# 04_ethernet.net
KiCad netlist of a schematic drawn in Altium Designer
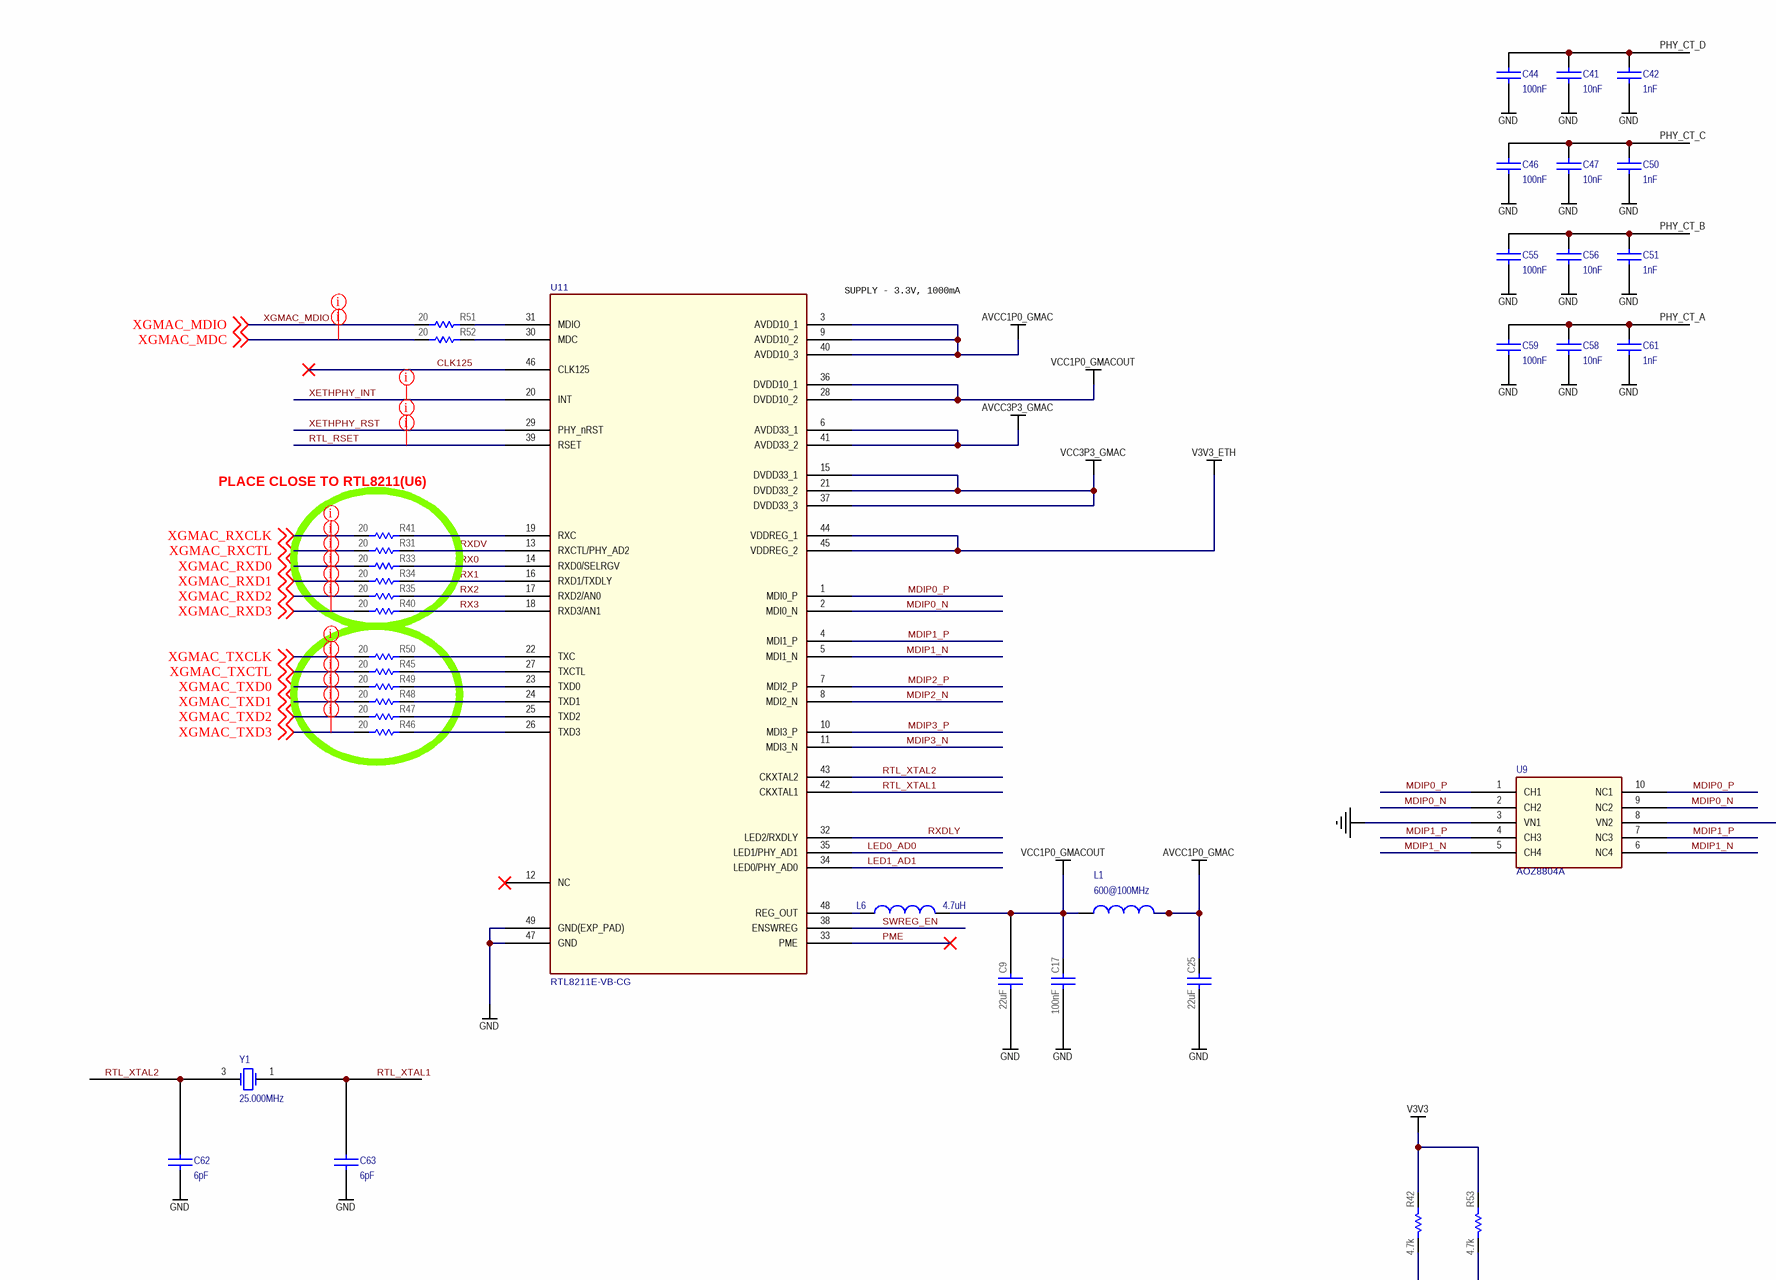
[diagram p0: 04_ethernet.SchDoc, top left]
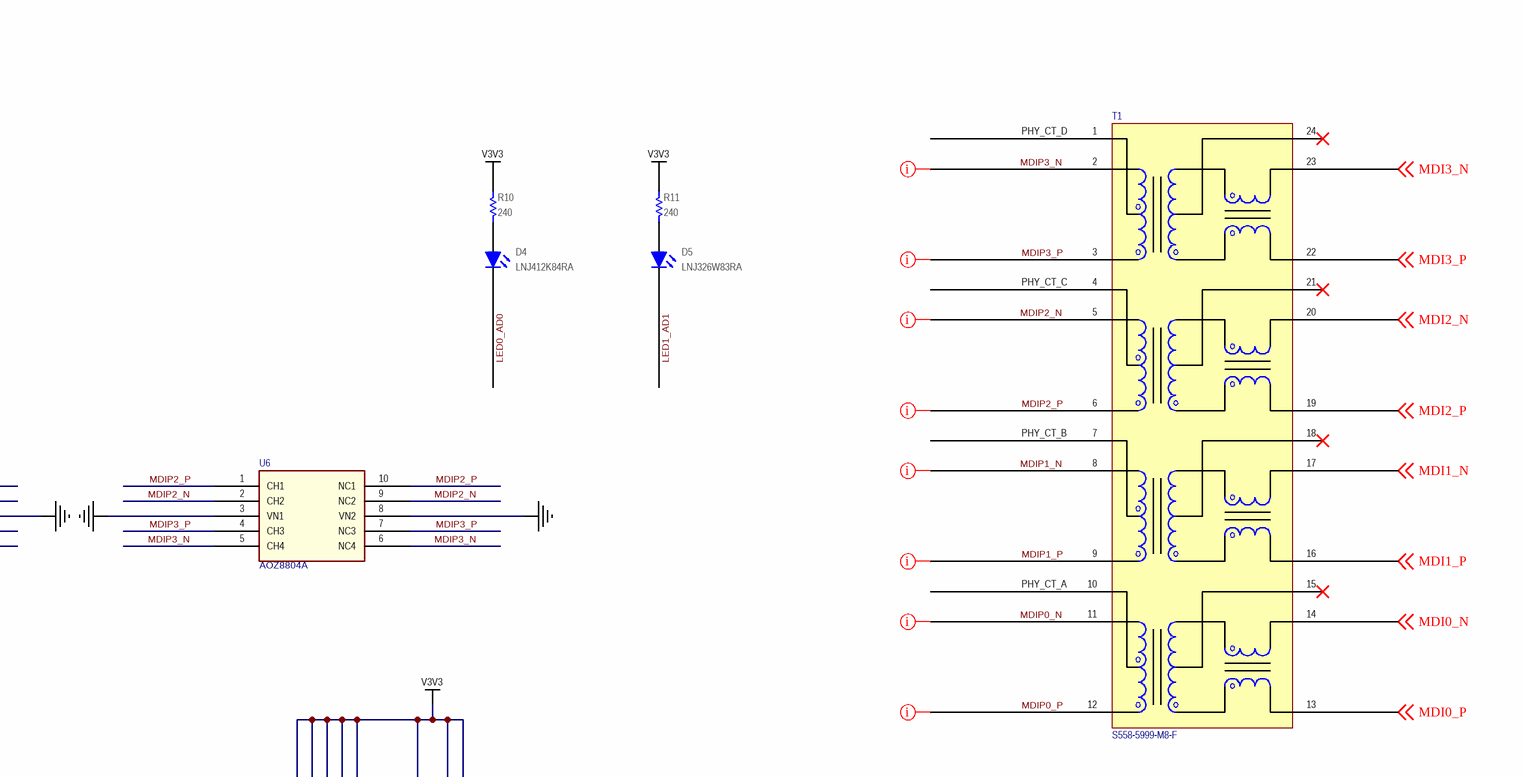
[diagram p1: 04_ethernet.SchDoc, top right]
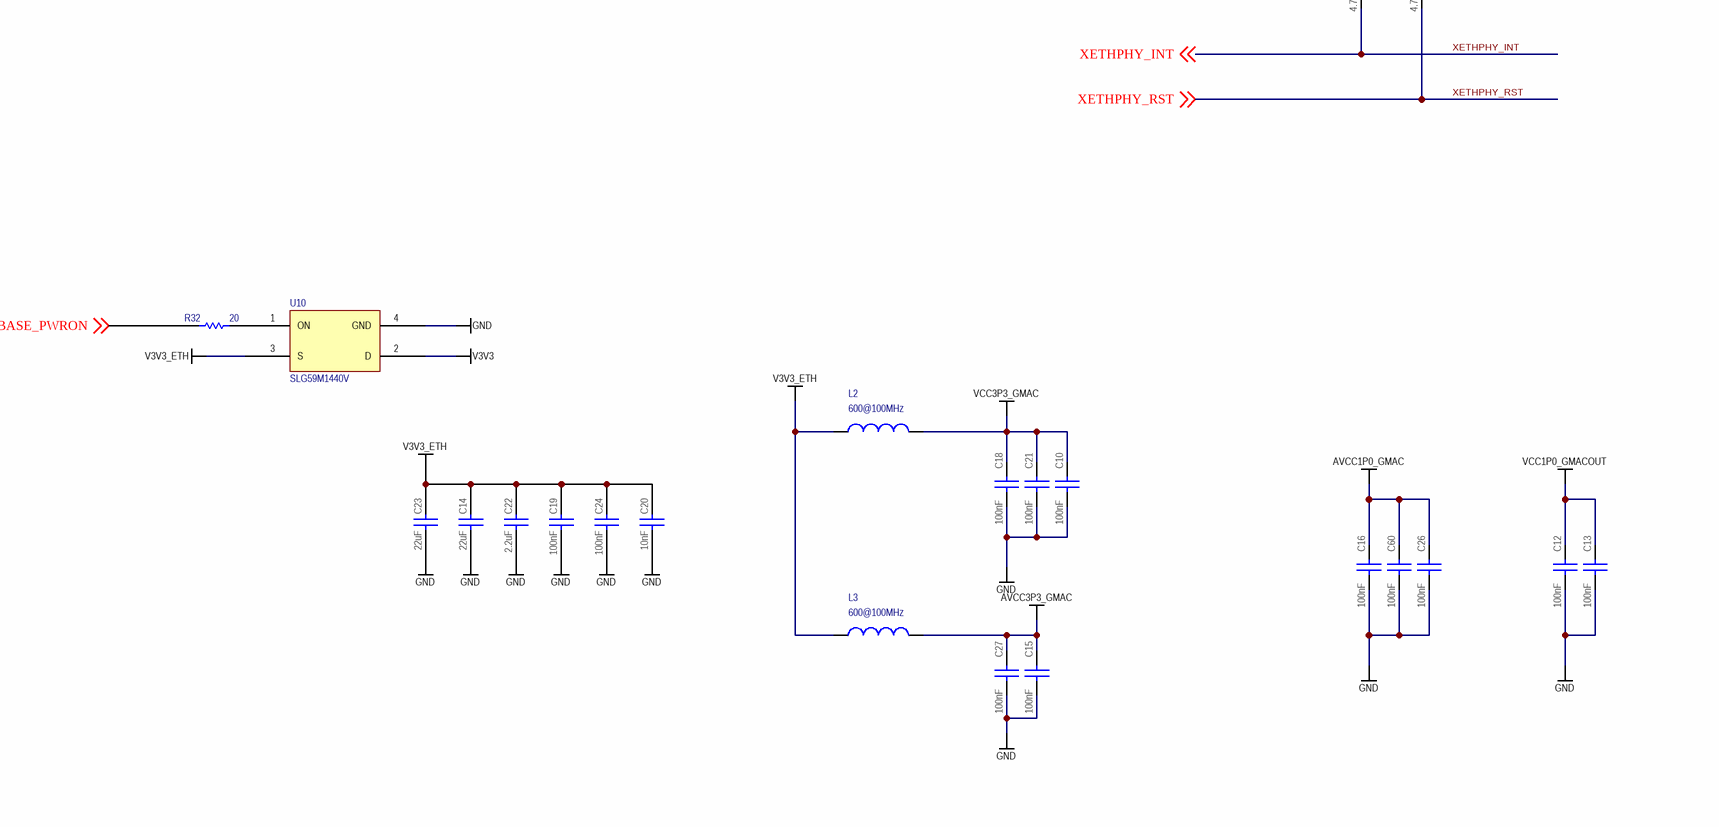
[diagram p2: 04_ethernet.SchDoc, bottom left]
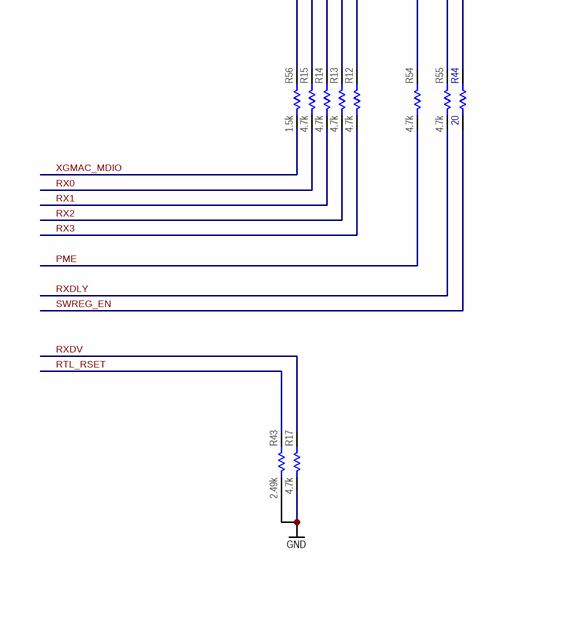
[diagram p3: 04_ethernet.SchDoc, bottom right]

(export (version "E")
  (design (tool "Eeschema 10.0.6"))
  (components
    (comp (ref "C9")
      (value "22uF")
      (footprint "CAPC200X125X145L45N")
      (description "Ceramic Capacitor 22uF ±20% 10V X7S 0805")
      (fields (field (name "MANUFACTURER") "TDK") (field (name "TOLERANCE") "±20%"))
      (libsource (lib "generic") (part "CAP"))
    )
    (comp (ref "C10")
      (value "100nF")
      (footprint "CAPC100X50X55L25N")
      (description "Ceramic Capacitor 100nF ±10% 50V X7R 0402")
      (fields (field (name "MANUFACTURER") "Murata") (field (name "TOLERANCE") "±10%"))
      (libsource (lib "generic") (part "CAP"))
    )
    (comp (ref "C12")
      (value "100nF")
      (footprint "CAPC100X50X55L25N")
      (description "Ceramic Capacitor 100nF ±10% 50V X7R 0402")
      (fields (field (name "MANUFACTURER") "Murata") (field (name "TOLERANCE") "±10%"))
      (libsource (lib "generic") (part "CAP"))
    )
    (comp (ref "C13")
      (value "100nF")
      (footprint "CAPC100X50X55L25N")
      (description "Ceramic Capacitor 100nF ±10% 50V X7R 0402")
      (fields (field (name "MANUFACTURER") "Murata") (field (name "TOLERANCE") "±10%"))
      (libsource (lib "generic") (part "CAP"))
    )
    (comp (ref "C14")
      (value "22uF")
      (footprint "CAPC200X125X145L45N")
      (description "Ceramic Capacitor 22uF ±20% 10V X7S 0805")
      (fields (field (name "MANUFACTURER") "TDK") (field (name "TOLERANCE") "±20%"))
      (libsource (lib "generic") (part "CAP"))
    )
    (comp (ref "C15")
      (value "100nF")
      (footprint "CAPC100X50X55L25N")
      (description "Ceramic Capacitor 100nF ±10% 50V X7R 0402")
      (fields (field (name "MANUFACTURER") "Murata") (field (name "TOLERANCE") "±10%"))
      (libsource (lib "generic") (part "CAP"))
    )
    (comp (ref "C16")
      (value "100nF")
      (footprint "CAPC100X50X55L25N")
      (description "Ceramic Capacitor 100nF ±10% 50V X7R 0402")
      (fields (field (name "MANUFACTURER") "Murata") (field (name "TOLERANCE") "±10%"))
      (libsource (lib "generic") (part "CAP"))
    )
    (comp (ref "C17")
      (value "100nF")
      (footprint "CAPC100X50X55L25N")
      (description "Ceramic Capacitor 100nF ±10% 50V X7R 0402")
      (fields (field (name "MANUFACTURER") "Murata") (field (name "TOLERANCE") "±10%"))
      (libsource (lib "generic") (part "CAP"))
    )
    (comp (ref "C18")
      (value "100nF")
      (footprint "CAPC100X50X55L25N")
      (description "Ceramic Capacitor 100nF ±10% 50V X7R 0402")
      (fields (field (name "MANUFACTURER") "Murata") (field (name "TOLERANCE") "±10%"))
      (libsource (lib "generic") (part "CAP"))
    )
    (comp (ref "C19")
      (value "100nF")
      (footprint "CAPC100X50X55L25N")
      (description "Ceramic Capacitor 100nF ±10% 50V X7R 0402")
      (fields (field (name "MANUFACTURER") "Murata") (field (name "TOLERANCE") "±10%"))
      (libsource (lib "generic") (part "CAP"))
    )
    (comp (ref "C20")
      (value "10nF")
      (footprint "CAPC100X50X55L25N")
      (description "Ceramic Capacitor 10nF ±10% 50V X7R 0402")
      (fields (field (name "MANUFACTURER") "Murata") (field (name "TOLERANCE") "±10%"))
      (libsource (lib "") (part "CAP_1"))
    )
    (comp (ref "C21")
      (value "100nF")
      (footprint "CAPC100X50X55L25N")
      (description "Ceramic Capacitor 100nF ±10% 50V X7R 0402")
      (fields (field (name "MANUFACTURER") "Murata") (field (name "TOLERANCE") "±10%"))
      (libsource (lib "generic") (part "CAP"))
    )
    (comp (ref "C22")
      (value "2.2uF")
      (footprint "CAPC160X80X90L20N")
      (description "Ceramic Capacitor 2.2uF ±20% 10V X7R 0603")
      (fields (field (name "MANUFACTURER") "TDK") (field (name "TOLERANCE") "±20%"))
      (libsource (lib "generic") (part "CAP"))
    )
    (comp (ref "C23")
      (value "22uF")
      (footprint "CAPC200X125X145L45N")
      (description "Ceramic Capacitor 22uF ±20% 10V X7S 0805")
      (fields (field (name "MANUFACTURER") "TDK") (field (name "TOLERANCE") "±20%"))
      (libsource (lib "generic") (part "CAP"))
    )
    (comp (ref "C24")
      (value "100nF")
      (footprint "CAPC100X50X55L25N")
      (description "Ceramic Capacitor 100nF ±10% 50V X7R 0402")
      (fields (field (name "MANUFACTURER") "Murata") (field (name "TOLERANCE") "±10%"))
      (libsource (lib "generic") (part "CAP"))
    )
    (comp (ref "C25")
      (value "22uF")
      (footprint "CAPC200X125X145L45N")
      (description "Ceramic Capacitor 22uF ±20% 10V X7S 0805")
      (fields (field (name "MANUFACTURER") "TDK") (field (name "TOLERANCE") "±20%"))
      (libsource (lib "generic") (part "CAP"))
    )
    (comp (ref "C26")
      (value "100nF")
      (footprint "CAPC100X50X55L25N")
      (description "Ceramic Capacitor 100nF ±10% 50V X7R 0402")
      (fields (field (name "MANUFACTURER") "Murata") (field (name "TOLERANCE") "±10%"))
      (libsource (lib "generic") (part "CAP"))
    )
    (comp (ref "C27")
      (value "100nF")
      (footprint "CAPC100X50X55L25N")
      (description "Ceramic Capacitor 100nF ±10% 50V X7R 0402")
      (fields (field (name "MANUFACTURER") "Murata") (field (name "TOLERANCE") "±10%"))
      (libsource (lib "generic") (part "CAP"))
    )
    (comp (ref "C41")
      (value "10nF")
      (footprint "generic:0402")
      (description "Ceramic Capacitor 10nF ±10% 25V X7R 0402")
      (fields (field (name "VOLTAGE") "25V") (field (name "MANUFACTURER") "Murata"))
      (libsource (lib "Graviton") (part "CAP 0402"))
    )
    (comp (ref "C42")
      (value "1nF")
      (footprint "generic:0402")
      (description "Ceramic Capacitor 1nF ±5% 50V NP0 0402")
      (fields (field (name "VOLTAGE") "50V") (field (name "MANUFACTURER") "Murata"))
      (libsource (lib "Graviton") (part "CAP 0402"))
    )
    (comp (ref "C44")
      (value "100nF")
      (footprint "generic:0402")
      (description "Ceramic Capacitor 100nF ±10% 16V X7R 0402")
      (fields (field (name "VOLTAGE") "16V") (field (name "MANUFACTURER") "Murata"))
      (libsource (lib "Graviton") (part "CAP 0402"))
    )
    (comp (ref "C46")
      (value "100nF")
      (footprint "generic:0402")
      (description "Ceramic Capacitor 100nF ±10% 16V X7R 0402")
      (fields (field (name "VOLTAGE") "16V") (field (name "MANUFACTURER") "Murata"))
      (libsource (lib "Graviton") (part "CAP 0402"))
    )
    (comp (ref "C47")
      (value "10nF")
      (footprint "generic:0402")
      (description "Ceramic Capacitor 10nF ±10% 25V X7R 0402")
      (fields (field (name "VOLTAGE") "25V") (field (name "MANUFACTURER") "Murata"))
      (libsource (lib "Graviton") (part "CAP 0402"))
    )
    (comp (ref "C50")
      (value "1nF")
      (footprint "generic:0402")
      (description "Ceramic Capacitor 1nF ±5% 50V NP0 0402")
      (fields (field (name "VOLTAGE") "50V") (field (name "MANUFACTURER") "Murata"))
      (libsource (lib "Graviton") (part "CAP 0402"))
    )
    (comp (ref "C51")
      (value "1nF")
      (footprint "generic:0402")
      (description "Ceramic Capacitor 1nF ±5% 50V NP0 0402")
      (fields (field (name "VOLTAGE") "50V") (field (name "MANUFACTURER") "Murata"))
      (libsource (lib "Graviton") (part "CAP 0402"))
    )
    (comp (ref "C55")
      (value "100nF")
      (footprint "generic:0402")
      (description "Ceramic Capacitor 100nF ±10% 16V X7R 0402")
      (fields (field (name "VOLTAGE") "16V") (field (name "MANUFACTURER") "Murata"))
      (libsource (lib "Graviton") (part "CAP 0402"))
    )
    (comp (ref "C56")
      (value "10nF")
      (footprint "generic:0402")
      (description "Ceramic Capacitor 10nF ±10% 25V X7R 0402")
      (fields (field (name "VOLTAGE") "25V") (field (name "MANUFACTURER") "Murata"))
      (libsource (lib "Graviton") (part "CAP 0402"))
    )
    (comp (ref "C58")
      (value "10nF")
      (footprint "generic:0402")
      (description "Ceramic Capacitor 10nF ±10% 25V X7R 0402")
      (fields (field (name "VOLTAGE") "25V") (field (name "MANUFACTURER") "Murata"))
      (libsource (lib "Graviton") (part "CAP 0402"))
    )
    (comp (ref "C59")
      (value "100nF")
      (footprint "generic:0402")
      (description "Ceramic Capacitor 100nF ±10% 16V X7R 0402")
      (fields (field (name "VOLTAGE") "16V") (field (name "MANUFACTURER") "Murata"))
      (libsource (lib "Graviton") (part "CAP 0402"))
    )
    (comp (ref "C60")
      (value "100nF")
      (footprint "CAPC100X50X55L25N")
      (description "Ceramic Capacitor 100nF ±10% 50V X7R 0402")
      (fields (field (name "MANUFACTURER") "Murata") (field (name "TOLERANCE") "±10%"))
      (libsource (lib "generic") (part "CAP"))
    )
    (comp (ref "C61")
      (value "1nF")
      (footprint "generic:0402")
      (description "Ceramic Capacitor 1nF ±5% 50V NP0 0402")
      (fields (field (name "VOLTAGE") "50V") (field (name "MANUFACTURER") "Murata"))
      (libsource (lib "Graviton") (part "CAP 0402"))
    )
    (comp (ref "C62")
      (value "6pF")
      (footprint "generic:0402")
      (description "Ceramic Capacitor 6pF ±0.25pF 50V NP0 RF 0402")
      (fields (field (name "VOLTAGE") "50V") (field (name "MANUFACTURER") "Murata"))
      (libsource (lib "Graviton") (part "CAP 0402"))
    )
    (comp (ref "C63")
      (value "6pF")
      (footprint "generic:0402")
      (description "Ceramic Capacitor 6pF ±0.25pF 50V NP0 RF 0402")
      (fields (field (name "VOLTAGE") "50V") (field (name "MANUFACTURER") "Murata"))
      (libsource (lib "Graviton") (part "CAP 0402"))
    )
    (comp (ref "D4")
      (value "LNJ412K84RA")
      (footprint "0603_LED")
      (description "LED, SMT 0603, Color Amber, 10mA, 2.05V")
      (fields (field (name "MANUFACTURER") "Panasonic"))
      (libsource (lib "generic") (part "LED0603Y"))
    )
    (comp (ref "D5")
      (value "LNJ326W83RA")
      (footprint "0603_LED")
      (description "LED, SMT 0603, Color Green, 10mA, 2.05V")
      (fields (field (name "MANUFACTURER") "Panasonic"))
      (libsource (lib "generic") (part "LED0603GR"))
    )
    (comp (ref "L1")
      (value "600@100MHz")
      (footprint "INDC1005X55N")
      (description "Ferrite Bead 600-Ohm @ 100MHz 900mA 0402")
      (fields (field (name "MANUFACTURER") "Murata") (field (name "TOLERANCE") "±25%"))
      (libsource (lib "altium-import") (part "root_0_IND 0402_"))
    )
    (comp (ref "L2")
      (value "600@100MHz")
      (footprint "INDC1005X55N")
      (description "Ferrite Bead 600-Ohm @ 100MHz 900mA 0402")
      (fields (field (name "MANUFACTURER") "Murata") (field (name "TOLERANCE") "±25%"))
      (libsource (lib "altium-import") (part "root_0_IND 0402_"))
    )
    (comp (ref "L3")
      (value "600@100MHz")
      (footprint "INDC1005X55N")
      (description "Ferrite Bead 600-Ohm @ 100MHz 900mA 0402")
      (fields (field (name "MANUFACTURER") "Murata") (field (name "TOLERANCE") "±25%"))
      (libsource (lib "altium-import") (part "root_0_IND 0402_"))
    )
    (comp (ref "L6")
      (value "4.7uH")
      (footprint "INDC200X125X105L50N")
      (description "4.7uH Inductor 750mA 260mOhm 0805")
      (fields (field (name "MANUFACTURER") "Samsung") (field (name "Comment") "CIG21L4R7MNE"))
      (libsource (lib "generic") (part "INDUCTOR"))
    )
    (comp (ref "R10")
      (value "240")
      (footprint "RESC1005X40N")
      (description "Thick Film Resistor 240 ±1% 0.1W 75V 0402")
      (fields (field (name "TOLERANCE") "±1%") (field (name "MANUFACTURER") "Panasonic"))
      (libsource (lib "generic") (part "RES"))
    )
    (comp (ref "R11")
      (value "240")
      (footprint "RESC1005X40N")
      (description "Thick Film Resistor 240 ±1% 0.1W 75V 0402")
      (fields (field (name "TOLERANCE") "±1%") (field (name "MANUFACTURER") "Panasonic"))
      (libsource (lib "generic") (part "RES"))
    )
    (comp (ref "R12")
      (value "4.7k")
      (footprint "RESC1005X40N")
      (description "Thick Film Resistor 4.7k ±1% 0.1W 75V 0402")
      (fields (field (name "TOLERANCE") "±1%") (field (name "MANUFACTURER") "Panasonic"))
      (libsource (lib "generic") (part "RES"))
    )
    (comp (ref "R13")
      (value "4.7k")
      (footprint "RESC1005X40N")
      (description "Thick Film Resistor 4.7k ±1% 0.1W 75V 0402")
      (fields (field (name "TOLERANCE") "±1%") (field (name "MANUFACTURER") "Panasonic"))
      (libsource (lib "generic") (part "RES"))
    )
    (comp (ref "R14")
      (value "4.7k")
      (footprint "RESC1005X40N")
      (description "Thick Film Resistor 4.7k ±1% 0.1W 75V 0402")
      (fields (field (name "TOLERANCE") "±1%") (field (name "MANUFACTURER") "Panasonic"))
      (libsource (lib "generic") (part "RES"))
    )
    (comp (ref "R15")
      (value "4.7k")
      (footprint "RESC1005X40N")
      (description "Thick Film Resistor 4.7k ±1% 0.1W 75V 0402")
      (fields (field (name "TOLERANCE") "±1%") (field (name "MANUFACTURER") "Panasonic"))
      (libsource (lib "generic") (part "RES"))
    )
    (comp (ref "R17")
      (value "4.7k")
      (footprint "RESC1005X40N")
      (description "Thick Film Resistor 4.7k ±1% 0.1W 75V 0402")
      (fields (field (name "TOLERANCE") "±1%") (field (name "MANUFACTURER") "Panasonic"))
      (libsource (lib "generic") (part "RES"))
    )
    (comp (ref "R31")
      (value "20")
      (footprint "RESC1005X40N")
      (description "Thick Film Resistor 20 ±1% 0.1W 75V 0402")
      (fields (field (name "TOLERANCE") "±1%") (field (name "MANUFACTURER") "Panasonic"))
      (libsource (lib "generic") (part "RES"))
    )
    (comp (ref "R32")
      (value "20")
      (footprint "generic:0402")
      (description "Thick Film Resistor 20 ±1% 0402")
      (fields (field (name "MANUFACTURER") "Panasonic") (field (name "TOLERANCE") "±1%"))
      (libsource (lib "altium-import") (part "root_2_RES 0402_"))
    )
    (comp (ref "R33")
      (value "20")
      (footprint "RESC1005X40N")
      (description "Thick Film Resistor 20 ±1% 0.1W 75V 0402")
      (fields (field (name "TOLERANCE") "±1%") (field (name "MANUFACTURER") "Panasonic"))
      (libsource (lib "generic") (part "RES"))
    )
    (comp (ref "R34")
      (value "20")
      (footprint "RESC1005X40N")
      (description "Thick Film Resistor 20 ±1% 0.1W 75V 0402")
      (fields (field (name "TOLERANCE") "±1%") (field (name "MANUFACTURER") "Panasonic"))
      (libsource (lib "generic") (part "RES"))
    )
    (comp (ref "R35")
      (value "20")
      (footprint "RESC1005X40N")
      (description "Thick Film Resistor 20 ±1% 0.1W 75V 0402")
      (fields (field (name "TOLERANCE") "±1%") (field (name "MANUFACTURER") "Panasonic"))
      (libsource (lib "generic") (part "RES"))
    )
    (comp (ref "R40")
      (value "20")
      (footprint "RESC1005X40N")
      (description "Thick Film Resistor 20 ±1% 0.1W 75V 0402")
      (fields (field (name "TOLERANCE") "±1%") (field (name "MANUFACTURER") "Panasonic"))
      (libsource (lib "generic") (part "RES"))
    )
    (comp (ref "R41")
      (value "20")
      (footprint "RESC1005X40N")
      (description "Thick Film Resistor 20 ±1% 0.1W 75V 0402")
      (fields (field (name "TOLERANCE") "±1%") (field (name "MANUFACTURER") "Panasonic"))
      (libsource (lib "generic") (part "RES"))
    )
    (comp (ref "R42")
      (value "4.7k")
      (footprint "RESC1005X40N")
      (description "Thick Film Resistor 4.7k ±1% 0.1W 75V 0402")
      (fields (field (name "TOLERANCE") "±1%") (field (name "MANUFACTURER") "Panasonic"))
      (libsource (lib "generic") (part "RES"))
    )
    (comp (ref "R43")
      (value "2.49k")
      (footprint "RESC1005X40N")
      (description "Thick Film Resistor 2.49k ±1% 0.1W 75V 0402")
      (fields (field (name "TOLERANCE") "±1%") (field (name "MANUFACTURER") "Panasonic"))
      (libsource (lib "generic") (part "RES"))
    )
    (comp (ref "R44")
      (value "20")
      (footprint "generic:0402")
      (description "Thick Film Resistor 20 ±1% 0402")
      (fields (field (name "MANUFACTURER") "Panasonic") (field (name "TOLERANCE") "±1%"))
      (libsource (lib "altium-import") (part "root_3_RES 0402_"))
    )
    (comp (ref "R45")
      (value "20")
      (footprint "RESC1005X40N")
      (description "Thick Film Resistor 20 ±1% 0.1W 75V 0402")
      (fields (field (name "TOLERANCE") "±1%") (field (name "MANUFACTURER") "Panasonic"))
      (libsource (lib "generic") (part "RES"))
    )
    (comp (ref "R46")
      (value "20")
      (footprint "RESC1005X40N")
      (description "Thick Film Resistor 20 ±1% 0.1W 75V 0402")
      (fields (field (name "TOLERANCE") "±1%") (field (name "MANUFACTURER") "Panasonic"))
      (libsource (lib "generic") (part "RES"))
    )
    (comp (ref "R47")
      (value "20")
      (footprint "RESC1005X40N")
      (description "Thick Film Resistor 20 ±1% 0.1W 75V 0402")
      (fields (field (name "TOLERANCE") "±1%") (field (name "MANUFACTURER") "Panasonic"))
      (libsource (lib "generic") (part "RES"))
    )
    (comp (ref "R48")
      (value "20")
      (footprint "RESC1005X40N")
      (description "Thick Film Resistor 20 ±1% 0.1W 75V 0402")
      (fields (field (name "TOLERANCE") "±1%") (field (name "MANUFACTURER") "Panasonic"))
      (libsource (lib "generic") (part "RES"))
    )
    (comp (ref "R49")
      (value "20")
      (footprint "RESC1005X40N")
      (description "Thick Film Resistor 20 ±1% 0.1W 75V 0402")
      (fields (field (name "TOLERANCE") "±1%") (field (name "MANUFACTURER") "Panasonic"))
      (libsource (lib "generic") (part "RES"))
    )
    (comp (ref "R50")
      (value "20")
      (footprint "RESC1005X40N")
      (description "Thick Film Resistor 20 ±1% 0.1W 75V 0402")
      (fields (field (name "TOLERANCE") "±1%") (field (name "MANUFACTURER") "Panasonic"))
      (libsource (lib "generic") (part "RES"))
    )
    (comp (ref "R51")
      (value "20")
      (footprint "RESC1005X40N")
      (description "Thick Film Resistor 20 ±1% 0.1W 75V 0402")
      (fields (field (name "TOLERANCE") "±1%") (field (name "MANUFACTURER") "Panasonic"))
      (libsource (lib "generic") (part "RES"))
    )
    (comp (ref "R52")
      (value "20")
      (footprint "RESC1005X40N")
      (description "Thick Film Resistor 20 ±1% 0.1W 75V 0402")
      (fields (field (name "TOLERANCE") "±1%") (field (name "MANUFACTURER") "Panasonic"))
      (libsource (lib "generic") (part "RES"))
    )
    (comp (ref "R53")
      (value "4.7k")
      (footprint "RESC1005X40N")
      (description "Thick Film Resistor 4.7k ±1% 0.1W 75V 0402")
      (fields (field (name "TOLERANCE") "±1%") (field (name "MANUFACTURER") "Panasonic"))
      (libsource (lib "generic") (part "RES"))
    )
    (comp (ref "R54")
      (value "4.7k")
      (footprint "RESC1005X40N")
      (description "Thick Film Resistor 4.7k ±1% 0.1W 75V 0402")
      (fields (field (name "TOLERANCE") "±1%") (field (name "MANUFACTURER") "Panasonic"))
      (libsource (lib "generic") (part "RES"))
    )
    (comp (ref "R55")
      (value "4.7k")
      (footprint "RESC1005X40N")
      (description "Thick Film Resistor 4.7k ±1% 0.1W 75V 0402")
      (fields (field (name "TOLERANCE") "±1%") (field (name "MANUFACTURER") "Panasonic"))
      (libsource (lib "generic") (part "RES"))
    )
    (comp (ref "R56")
      (value "1.5k")
      (footprint "RESC1005X40N")
      (description "Thick Film Resistor 1.5k ±1% 0.1W 75V 0402")
      (fields (field (name "TOLERANCE") "±1%") (field (name "MANUFACTURER") "Panasonic"))
      (libsource (lib "generic") (part "RES"))
    )
    (comp (ref "T1")
      (value "S558-5999-M8-F")
      (footprint "SOIC127P1524X571-24N")
      (description "Gigabit LAN transformer")
      (fields (field (name "MANUFACTURER") "Bel Fuse"))
      (libsource (lib "bel-fuse") (part "S558-5999-M8-F"))
    )
    (comp (ref "U6")
      (value "AOZ8804A")
      (footprint "AOZ8804")
      (description "Ultra-low Capacitance TVS Diodes")
      (fields (field (name "MANUFACTURER") "Alpha & Omega"))
      (libsource (lib "*") (part "ICMEF112P900MFR_5"))
    )
    (comp (ref "U9")
      (value "AOZ8804A")
      (footprint "AOZ8804")
      (description "Ultra-low Capacitance TVS Diodes")
      (fields (field (name "MANUFACTURER") "Alpha & Omega"))
      (libsource (lib "*") (part "ICMEF112P900MFR_5"))
    )
    (comp (ref "U10")
      (value "SLG59M1440V")
      (footprint "silego:SLG59M1440V")
      (description "Ultra-small 1.5A High-Side Load Switch")
      (fields (field (name "MANUFACTURER") "Silego"))
      (libsource (lib "silego") (part "SLG59M1440V"))
    )
    (comp (ref "U11")
      (value "RTL8211E-VB-CG")
      (footprint "realtek:QFN48")
      (description "Gigabit Ethernet Transceiver")
      (fields (field (name "MANUFACTURER") "Realtek"))
      (libsource (lib "*") (part "CON_40P_6.5mm"))
    )
    (comp (ref "Y1")
      (value "XRCGB25M000F3N00R0")
      (footprint "XRCGB")
      (description "CRYSTAL, 25.000MHz, 30ppm, 6pF")
      (fields (field (name "MANUFACTURER") "Murata") (field (name "FREQ") "25.000MHz"))
      (libsource (lib "murata") (part "XRCGB25M000F3N00R0"))
    )
  )
  (nets
    (net (code "1") (name "/CLK125") (class "Default")
      (node (ref "U11") (pin "46") (pinfunction "CLK125_46") (pintype "passive+no_connect"))
    )
    (net (code "2") (name "/LED0_AD0") (class "Default")
      (node (ref "D4") (pin "2") (pinfunction "K_2") (pintype "passive"))
      (node (ref "U11") (pin "35") (pinfunction "LED1/PHY_AD1_35") (pintype "passive"))
    )
    (net (code "3") (name "/LED1_AD1") (class "Default")
      (node (ref "D5") (pin "2") (pinfunction "K_2") (pintype "passive"))
      (node (ref "U11") (pin "34") (pinfunction "LED0/PHY_AD0_34") (pintype "passive"))
    )
    (net (code "4") (name "/MDIP0_N") (class "Default")
      (node (ref "T1") (pin "11") (pinfunction "TPONA_11") (pintype "passive"))
      (node (ref "U11") (pin "2") (pinfunction "MDI0_N_2") (pintype "passive"))
      (node (ref "U9") (pin "2") (pinfunction "CH2_2") (pintype "passive"))
      (node (ref "U9") (pin "9") (pinfunction "NC2_9") (pintype "passive"))
    )
    (net (code "5") (name "/MDIP0_P") (class "Default")
      (node (ref "T1") (pin "12") (pinfunction "TPOPA_12") (pintype "passive"))
      (node (ref "U11") (pin "1") (pinfunction "MDI0_P_1") (pintype "passive"))
      (node (ref "U9") (pin "1") (pinfunction "CH1_1") (pintype "passive"))
      (node (ref "U9") (pin "10") (pinfunction "NC1_10") (pintype "passive"))
    )
    (net (code "6") (name "/MDIP1_N") (class "Default")
      (node (ref "T1") (pin "8") (pinfunction "TPONB_8") (pintype "passive"))
      (node (ref "U11") (pin "5") (pinfunction "MDI1_N_5") (pintype "passive"))
      (node (ref "U9") (pin "5") (pinfunction "CH4_5") (pintype "power_in"))
      (node (ref "U9") (pin "6") (pinfunction "NC4_6") (pintype "power_in"))
    )
    (net (code "7") (name "/MDIP1_P") (class "Default")
      (node (ref "T1") (pin "9") (pinfunction "TPOPB_9") (pintype "passive"))
      (node (ref "U11") (pin "4") (pinfunction "MDI1_P_4") (pintype "passive"))
      (node (ref "U9") (pin "4") (pinfunction "CH3_4") (pintype "passive"))
      (node (ref "U9") (pin "7") (pinfunction "NC3_7") (pintype "passive"))
    )
    (net (code "8") (name "/MDIP2_N") (class "Default")
      (node (ref "T1") (pin "5") (pinfunction "TPONC_5") (pintype "passive"))
      (node (ref "U11") (pin "8") (pinfunction "MDI2_N_8") (pintype "passive"))
      (node (ref "U6") (pin "2") (pinfunction "CH2_2") (pintype "passive"))
      (node (ref "U6") (pin "9") (pinfunction "NC2_9") (pintype "passive"))
    )
    (net (code "9") (name "/MDIP2_P") (class "Default")
      (node (ref "T1") (pin "6") (pinfunction "TPOPC_6") (pintype "passive"))
      (node (ref "U11") (pin "7") (pinfunction "MDI2_P_7") (pintype "passive"))
      (node (ref "U6") (pin "1") (pinfunction "CH1_1") (pintype "passive"))
      (node (ref "U6") (pin "10") (pinfunction "NC1_10") (pintype "passive"))
    )
    (net (code "10") (name "/MDIP3_N") (class "Default")
      (node (ref "T1") (pin "2") (pinfunction "TPOND_2") (pintype "passive"))
      (node (ref "U11") (pin "11") (pinfunction "MDI3_N_11") (pintype "passive"))
      (node (ref "U6") (pin "5") (pinfunction "CH4_5") (pintype "power_in"))
      (node (ref "U6") (pin "6") (pinfunction "NC4_6") (pintype "power_in"))
    )
    (net (code "11") (name "/MDIP3_P") (class "Default")
      (node (ref "T1") (pin "3") (pinfunction "TPOPD_3") (pintype "passive"))
      (node (ref "U11") (pin "10") (pinfunction "MDI3_P_10") (pintype "passive"))
      (node (ref "U6") (pin "4") (pinfunction "CH3_4") (pintype "passive"))
      (node (ref "U6") (pin "7") (pinfunction "NC3_7") (pintype "passive"))
    )
    (net (code "12") (name "/PHY_CT_A") (class "Default")
      (node (ref "C58") (pin "2") (pinfunction "2_2") (pintype "passive"))
      (node (ref "C59") (pin "2") (pinfunction "2_2") (pintype "passive"))
      (node (ref "C61") (pin "2") (pinfunction "2_2") (pintype "passive"))
      (node (ref "T1") (pin "10") (pinfunction "TCTA_10") (pintype "passive"))
    )
    (net (code "13") (name "/PHY_CT_B") (class "Default")
      (node (ref "C51") (pin "2") (pinfunction "2_2") (pintype "passive"))
      (node (ref "C55") (pin "2") (pinfunction "2_2") (pintype "passive"))
      (node (ref "C56") (pin "2") (pinfunction "2_2") (pintype "passive"))
      (node (ref "T1") (pin "7") (pinfunction "TCTB_7") (pintype "passive"))
    )
    (net (code "14") (name "/PHY_CT_C") (class "Default")
      (node (ref "C46") (pin "2") (pinfunction "2_2") (pintype "passive"))
      (node (ref "C47") (pin "2") (pinfunction "2_2") (pintype "passive"))
      (node (ref "C50") (pin "2") (pinfunction "2_2") (pintype "passive"))
      (node (ref "T1") (pin "4") (pinfunction "TCTC_4") (pintype "passive"))
    )
    (net (code "15") (name "/PHY_CT_D") (class "Default")
      (node (ref "C41") (pin "2") (pinfunction "2_2") (pintype "passive"))
      (node (ref "C42") (pin "2") (pinfunction "2_2") (pintype "passive"))
      (node (ref "C44") (pin "2") (pinfunction "2_2") (pintype "passive"))
      (node (ref "T1") (pin "1") (pinfunction "TCTD_1") (pintype "passive"))
    )
    (net (code "16") (name "/PME") (class "Default")
      (node (ref "R54") (pin "1") (pinfunction "1_1") (pintype "passive"))
      (node (ref "U11") (pin "33") (pinfunction "PME_33") (pintype "passive"))
    )
    (net (code "17") (name "/RTL_RSET") (class "Default")
      (node (ref "R43") (pin "1") (pinfunction "1_1") (pintype "passive"))
      (node (ref "U11") (pin "39") (pinfunction "RSET_39") (pintype "passive"))
    )
    (net (code "18") (name "/RTL_XTAL1") (class "Default")
      (node (ref "C63") (pin "2") (pinfunction "2_2") (pintype "passive"))
      (node (ref "U11") (pin "42") (pinfunction "CKXTAL1_42") (pintype "passive"))
      (node (ref "Y1") (pin "1") (pinfunction "OSC1_1") (pintype "passive"))
    )
    (net (code "19") (name "/RTL_XTAL2") (class "Default")
      (node (ref "C62") (pin "2") (pinfunction "2_2") (pintype "passive"))
      (node (ref "U11") (pin "43") (pinfunction "CKXTAL2_43") (pintype "passive"))
      (node (ref "Y1") (pin "3") (pinfunction "OSC2_3") (pintype "passive"))
    )
    (net (code "20") (name "/RX0") (class "Default")
      (node (ref "R15") (pin "1") (pinfunction "1_1") (pintype "passive"))
      (node (ref "R33") (pin "2") (pinfunction "2_2") (pintype "passive"))
      (node (ref "U11") (pin "14") (pinfunction "RXD0/SELRGV_14") (pintype "passive"))
    )
    (net (code "21") (name "/RX1") (class "Default")
      (node (ref "R14") (pin "1") (pinfunction "1_1") (pintype "passive"))
      (node (ref "R34") (pin "2") (pinfunction "2_2") (pintype "passive"))
      (node (ref "U11") (pin "16") (pinfunction "RXD1/TXDLY_16") (pintype "passive"))
    )
    (net (code "22") (name "/RX2") (class "Default")
      (node (ref "R13") (pin "1") (pinfunction "1_1") (pintype "passive"))
      (node (ref "R35") (pin "2") (pinfunction "2_2") (pintype "passive"))
      (node (ref "U11") (pin "17") (pinfunction "RXD2/AN0_17") (pintype "passive"))
    )
    (net (code "23") (name "/RX3") (class "Default")
      (node (ref "R12") (pin "1") (pinfunction "1_1") (pintype "passive"))
      (node (ref "R40") (pin "2") (pinfunction "2_2") (pintype "passive"))
      (node (ref "U11") (pin "18") (pinfunction "RXD3/AN1_18") (pintype "passive"))
    )
    (net (code "24") (name "/RXDLY") (class "Default")
      (node (ref "R55") (pin "1") (pinfunction "1_1") (pintype "passive"))
      (node (ref "U11") (pin "32") (pinfunction "LED2/RXDLY_32") (pintype "passive"))
    )
    (net (code "25") (name "/RXDV") (class "Default")
      (node (ref "R17") (pin "2") (pinfunction "2_2") (pintype "passive"))
      (node (ref "R31") (pin "2") (pinfunction "2_2") (pintype "passive"))
      (node (ref "U11") (pin "13") (pinfunction "RXCTL/PHY_AD2_13") (pintype "passive"))
    )
    (net (code "26") (name "/SWREG_EN") (class "Default")
      (node (ref "R44") (pin "2") (pinfunction "2_2") (pintype "passive"))
      (node (ref "U11") (pin "38") (pinfunction "ENSWREG_38") (pintype "passive"))
    )
    (net (code "27") (name "AVCC1P0_GMAC") (class "Default")
      (node (ref "C16") (pin "2") (pinfunction "2_2") (pintype "passive"))
      (node (ref "C25") (pin "2") (pinfunction "2_2") (pintype "passive"))
      (node (ref "C26") (pin "2") (pinfunction "2_2") (pintype "passive"))
      (node (ref "C60") (pin "2") (pinfunction "2_2") (pintype "passive"))
      (node (ref "L1") (pin "2") (pinfunction "2_2") (pintype "passive"))
      (node (ref "U11") (pin "3") (pinfunction "AVDD10_1_3") (pintype "passive"))
      (node (ref "U11") (pin "40") (pinfunction "AVDD10_3_40") (pintype "passive"))
      (node (ref "U11") (pin "9") (pinfunction "AVDD10_2_9") (pintype "passive"))
    )
    (net (code "28") (name "AVCC3P3_GMAC") (class "Default")
      (node (ref "C15") (pin "2") (pinfunction "2_2") (pintype "passive"))
      (node (ref "C27") (pin "2") (pinfunction "2_2") (pintype "passive"))
      (node (ref "L3") (pin "2") (pinfunction "2_2") (pintype "passive"))
      (node (ref "U11") (pin "41") (pinfunction "AVDD33_2_41") (pintype "passive"))
      (node (ref "U11") (pin "6") (pinfunction "AVDD33_1_6") (pintype "passive"))
    )
    (net (code "29") (name "GND") (class "Default")
      (node (ref "C10") (pin "1") (pinfunction "1_1") (pintype "passive"))
      (node (ref "C12") (pin "1") (pinfunction "1_1") (pintype "passive"))
      (node (ref "C13") (pin "1") (pinfunction "1_1") (pintype "passive"))
      (node (ref "C14") (pin "1") (pinfunction "1_1") (pintype "passive"))
      (node (ref "C15") (pin "1") (pinfunction "1_1") (pintype "passive"))
      (node (ref "C16") (pin "1") (pinfunction "1_1") (pintype "passive"))
      (node (ref "C17") (pin "1") (pinfunction "1_1") (pintype "passive"))
      (node (ref "C18") (pin "1") (pinfunction "1_1") (pintype "passive"))
      (node (ref "C19") (pin "1") (pinfunction "1_1") (pintype "passive"))
      (node (ref "C20") (pin "2") (pinfunction "2_2") (pintype "passive"))
      (node (ref "C21") (pin "1") (pinfunction "1_1") (pintype "passive"))
      (node (ref "C22") (pin "1") (pinfunction "1_1") (pintype "passive"))
      (node (ref "C23") (pin "1") (pinfunction "1_1") (pintype "passive"))
      (node (ref "C24") (pin "1") (pinfunction "1_1") (pintype "passive"))
      (node (ref "C25") (pin "1") (pinfunction "1_1") (pintype "passive"))
      (node (ref "C26") (pin "1") (pinfunction "1_1") (pintype "passive"))
      (node (ref "C27") (pin "1") (pinfunction "1_1") (pintype "passive"))
      (node (ref "C41") (pin "1") (pinfunction "1_1") (pintype "passive"))
      (node (ref "C42") (pin "1") (pinfunction "1_1") (pintype "passive"))
      (node (ref "C44") (pin "1") (pinfunction "1_1") (pintype "passive"))
      (node (ref "C46") (pin "1") (pinfunction "1_1") (pintype "passive"))
      (node (ref "C47") (pin "1") (pinfunction "1_1") (pintype "passive"))
      (node (ref "C50") (pin "1") (pinfunction "1_1") (pintype "passive"))
      (node (ref "C51") (pin "1") (pinfunction "1_1") (pintype "passive"))
      (node (ref "C55") (pin "1") (pinfunction "1_1") (pintype "passive"))
      (node (ref "C56") (pin "1") (pinfunction "1_1") (pintype "passive"))
      (node (ref "C58") (pin "1") (pinfunction "1_1") (pintype "passive"))
      (node (ref "C59") (pin "1") (pinfunction "1_1") (pintype "passive"))
      (node (ref "C60") (pin "1") (pinfunction "1_1") (pintype "passive"))
      (node (ref "C61") (pin "1") (pinfunction "1_1") (pintype "passive"))
      (node (ref "C62") (pin "1") (pinfunction "1_1") (pintype "passive"))
      (node (ref "C63") (pin "1") (pinfunction "1_1") (pintype "passive"))
      (node (ref "C9") (pin "1") (pinfunction "1_1") (pintype "passive"))
      (node (ref "R17") (pin "1") (pinfunction "1_1") (pintype "passive"))
      (node (ref "R43") (pin "2") (pinfunction "2_2") (pintype "passive"))
      (node (ref "U10") (pin "4") (pinfunction "GND_4") (pintype "passive"))
      (node (ref "U11") (pin "47") (pinfunction "GND_47") (pintype "passive"))
      (node (ref "U11") (pin "49") (pinfunction "GND(EXP_PAD)_49") (pintype "passive"))
      (node (ref "U6") (pin "3") (pinfunction "VN1_3") (pintype "passive"))
      (node (ref "U6") (pin "8") (pinfunction "VN2_8") (pintype "passive"))
      (node (ref "U9") (pin "3") (pinfunction "VN1_3") (pintype "passive"))
      (node (ref "U9") (pin "8") (pinfunction "VN2_8") (pintype "passive"))
    )
    (net (code "30") (name "MDI0_N") (class "Default")
      (node (ref "T1") (pin "14") (pinfunction "TXONA_14") (pintype "passive"))
    )
    (net (code "31") (name "MDI0_P") (class "Default")
      (node (ref "T1") (pin "13") (pinfunction "TXOPA_13") (pintype "passive"))
    )
    (net (code "32") (name "MDI1_N") (class "Default")
      (node (ref "T1") (pin "17") (pinfunction "TXONB_17") (pintype "passive"))
    )
    (net (code "33") (name "MDI1_P") (class "Default")
      (node (ref "T1") (pin "16") (pinfunction "TXOPB_16") (pintype "passive"))
    )
    (net (code "34") (name "MDI2_N") (class "Default")
      (node (ref "T1") (pin "20") (pinfunction "TXONC_20") (pintype "passive"))
    )
    (net (code "35") (name "MDI2_P") (class "Default")
      (node (ref "T1") (pin "19") (pinfunction "TXOPC_19") (pintype "passive"))
    )
    (net (code "36") (name "MDI3_N") (class "Default")
      (node (ref "T1") (pin "23") (pinfunction "TXOND_23") (pintype "passive"))
    )
    (net (code "37") (name "MDI3_P") (class "Default")
      (node (ref "T1") (pin "22") (pinfunction "TXOPD_22") (pintype "passive"))
    )
    (net (code "38") (name "Net-(D4-A)") (class "Default")
      (node (ref "D4") (pin "1") (pinfunction "A_1") (pintype "passive"))
      (node (ref "R10") (pin "2") (pinfunction "2_2") (pintype "passive"))
    )
    (net (code "39") (name "Net-(D5-A)") (class "Default")
      (node (ref "D5") (pin "1") (pinfunction "A_1") (pintype "passive"))
      (node (ref "R11") (pin "2") (pinfunction "2_2") (pintype "passive"))
    )
    (net (code "40") (name "Net-(U10-ON)") (class "Default")
      (node (ref "R32") (pin "1") (pinfunction "1_1") (pintype "passive"))
      (node (ref "U10") (pin "1") (pinfunction "ON_1") (pintype "passive"))
    )
    (net (code "41") (name "Net-(U11-MDC)") (class "Default")
      (node (ref "R52") (pin "2") (pinfunction "2_2") (pintype "passive"))
      (node (ref "U11") (pin "30") (pinfunction "MDC_30") (pintype "passive"))
    )
    (net (code "42") (name "Net-(U11-MDIO)") (class "Default")
      (node (ref "R51") (pin "2") (pinfunction "2_2") (pintype "passive"))
      (node (ref "U11") (pin "31") (pinfunction "MDIO_31") (pintype "passive"))
    )
    (net (code "43") (name "Net-(U11-REG_OUT)") (class "Default")
      (node (ref "L6") (pin "1") (pinfunction "1_1") (pintype "passive"))
      (node (ref "U11") (pin "48") (pinfunction "REG_OUT_48") (pintype "passive"))
    )
    (net (code "44") (name "Net-(U11-RXC)") (class "Default")
      (node (ref "R41") (pin "2") (pinfunction "2_2") (pintype "passive"))
      (node (ref "U11") (pin "19") (pinfunction "RXC_19") (pintype "passive"))
    )
    (net (code "45") (name "Net-(U11-TXC)") (class "Default")
      (node (ref "R50") (pin "2") (pinfunction "2_2") (pintype "passive"))
      (node (ref "U11") (pin "22") (pinfunction "TXC_22") (pintype "passive"))
    )
    (net (code "46") (name "Net-(U11-TXCTL)") (class "Default")
      (node (ref "R45") (pin "2") (pinfunction "2_2") (pintype "passive"))
      (node (ref "U11") (pin "27") (pinfunction "TXCTL_27") (pintype "passive"))
    )
    (net (code "47") (name "Net-(U11-TXD0)") (class "Default")
      (node (ref "R49") (pin "2") (pinfunction "2_2") (pintype "passive"))
      (node (ref "U11") (pin "23") (pinfunction "TXD0_23") (pintype "passive"))
    )
    (net (code "48") (name "Net-(U11-TXD1)") (class "Default")
      (node (ref "R48") (pin "2") (pinfunction "2_2") (pintype "passive"))
      (node (ref "U11") (pin "24") (pinfunction "TXD1_24") (pintype "passive"))
    )
    (net (code "49") (name "Net-(U11-TXD2)") (class "Default")
      (node (ref "R47") (pin "2") (pinfunction "2_2") (pintype "passive"))
      (node (ref "U11") (pin "25") (pinfunction "TXD2_25") (pintype "passive"))
    )
    (net (code "50") (name "Net-(U11-TXD3)") (class "Default")
      (node (ref "R46") (pin "2") (pinfunction "2_2") (pintype "passive"))
      (node (ref "U11") (pin "26") (pinfunction "TXD3_26") (pintype "passive"))
    )
    (net (code "51") (name "V3V3") (class "Default")
      (node (ref "R10") (pin "1") (pinfunction "1_1") (pintype "passive"))
      (node (ref "R11") (pin "1") (pinfunction "1_1") (pintype "passive"))
      (node (ref "R12") (pin "2") (pinfunction "2_2") (pintype "passive"))
      (node (ref "R13") (pin "2") (pinfunction "2_2") (pintype "passive"))
      (node (ref "R14") (pin "2") (pinfunction "2_2") (pintype "passive"))
      (node (ref "R15") (pin "2") (pinfunction "2_2") (pintype "passive"))
      (node (ref "R42") (pin "2") (pinfunction "2_2") (pintype "passive"))
      (node (ref "R44") (pin "1") (pinfunction "1_1") (pintype "passive"))
      (node (ref "R53") (pin "2") (pinfunction "2_2") (pintype "passive"))
      (node (ref "R54") (pin "2") (pinfunction "2_2") (pintype "passive"))
      (node (ref "R55") (pin "2") (pinfunction "2_2") (pintype "passive"))
      (node (ref "R56") (pin "1") (pinfunction "1_1") (pintype "passive"))
      (node (ref "U10") (pin "2") (pinfunction "D_2") (pintype "passive"))
    )
    (net (code "52") (name "V3V3_ETH") (class "Default")
      (node (ref "C14") (pin "2") (pinfunction "2_2") (pintype "passive"))
      (node (ref "C19") (pin "2") (pinfunction "2_2") (pintype "passive"))
      (node (ref "C20") (pin "1") (pinfunction "1_1") (pintype "passive"))
      (node (ref "C22") (pin "2") (pinfunction "2_2") (pintype "passive"))
      (node (ref "C23") (pin "2") (pinfunction "2_2") (pintype "passive"))
      (node (ref "C24") (pin "2") (pinfunction "2_2") (pintype "passive"))
      (node (ref "L2") (pin "1") (pinfunction "1_1") (pintype "passive"))
      (node (ref "L3") (pin "1") (pinfunction "1_1") (pintype "passive"))
      (node (ref "U10") (pin "3") (pinfunction "S_3") (pintype "passive"))
      (node (ref "U11") (pin "44") (pinfunction "VDDREG_1_44") (pintype "passive"))
      (node (ref "U11") (pin "45") (pinfunction "VDDREG_2_45") (pintype "passive"))
    )
    (net (code "53") (name "VCC1P0_GMACOUT") (class "Default")
      (node (ref "C12") (pin "2") (pinfunction "2_2") (pintype "passive"))
      (node (ref "C13") (pin "2") (pinfunction "2_2") (pintype "passive"))
      (node (ref "C17") (pin "2") (pinfunction "2_2") (pintype "passive"))
      (node (ref "C9") (pin "2") (pinfunction "2_2") (pintype "passive"))
      (node (ref "L1") (pin "1") (pinfunction "1_1") (pintype "passive"))
      (node (ref "L6") (pin "2") (pinfunction "2_2") (pintype "passive"))
      (node (ref "U11") (pin "28") (pinfunction "DVDD10_2_28") (pintype "passive"))
      (node (ref "U11") (pin "36") (pinfunction "DVDD10_1_36") (pintype "passive"))
    )
    (net (code "54") (name "VCC3P3_GMAC") (class "Default")
      (node (ref "C10") (pin "2") (pinfunction "2_2") (pintype "passive"))
      (node (ref "C18") (pin "2") (pinfunction "2_2") (pintype "passive"))
      (node (ref "C21") (pin "2") (pinfunction "2_2") (pintype "passive"))
      (node (ref "L2") (pin "2") (pinfunction "2_2") (pintype "passive"))
      (node (ref "U11") (pin "15") (pinfunction "DVDD33_1_15") (pintype "passive"))
      (node (ref "U11") (pin "21") (pinfunction "DVDD33_2_21") (pintype "passive"))
      (node (ref "U11") (pin "37") (pinfunction "DVDD33_3_37") (pintype "passive"))
    )
    (net (code "55") (name "XBASE_PWRON") (class "Default")
      (node (ref "R32") (pin "2") (pinfunction "2_2") (pintype "passive"))
    )
    (net (code "56") (name "XETHPHY_INT") (class "Default")
      (node (ref "R42") (pin "1") (pinfunction "1_1") (pintype "passive"))
      (node (ref "U11") (pin "20") (pinfunction "INT_20") (pintype "passive"))
    )
    (net (code "57") (name "XETHPHY_RST") (class "Default")
      (node (ref "R53") (pin "1") (pinfunction "1_1") (pintype "passive"))
      (node (ref "U11") (pin "29") (pinfunction "PHY_nRST_29") (pintype "passive"))
    )
    (net (code "58") (name "XGMAC_MDC") (class "Default")
      (node (ref "R52") (pin "1") (pinfunction "1_1") (pintype "passive"))
    )
    (net (code "59") (name "XGMAC_MDIO") (class "Default")
      (node (ref "R51") (pin "1") (pinfunction "1_1") (pintype "passive"))
      (node (ref "R56") (pin "2") (pinfunction "2_2") (pintype "passive"))
    )
    (net (code "60") (name "XGMAC_RXCLK") (class "Default")
      (node (ref "R41") (pin "1") (pinfunction "1_1") (pintype "passive"))
    )
    (net (code "61") (name "XGMAC_RXCTL") (class "Default")
      (node (ref "R31") (pin "1") (pinfunction "1_1") (pintype "passive"))
    )
    (net (code "62") (name "XGMAC_RXD0") (class "Default")
      (node (ref "R33") (pin "1") (pinfunction "1_1") (pintype "passive"))
    )
    (net (code "63") (name "XGMAC_RXD1") (class "Default")
      (node (ref "R34") (pin "1") (pinfunction "1_1") (pintype "passive"))
    )
    (net (code "64") (name "XGMAC_RXD2") (class "Default")
      (node (ref "R35") (pin "1") (pinfunction "1_1") (pintype "passive"))
    )
    (net (code "65") (name "XGMAC_RXD3") (class "Default")
      (node (ref "R40") (pin "1") (pinfunction "1_1") (pintype "passive"))
    )
    (net (code "66") (name "XGMAC_TXCLK") (class "Default")
      (node (ref "R50") (pin "1") (pinfunction "1_1") (pintype "passive"))
    )
    (net (code "67") (name "XGMAC_TXCTL") (class "Default")
      (node (ref "R45") (pin "1") (pinfunction "1_1") (pintype "passive"))
    )
    (net (code "68") (name "XGMAC_TXD0") (class "Default")
      (node (ref "R49") (pin "1") (pinfunction "1_1") (pintype "passive"))
    )
    (net (code "69") (name "XGMAC_TXD1") (class "Default")
      (node (ref "R48") (pin "1") (pinfunction "1_1") (pintype "passive"))
    )
    (net (code "70") (name "XGMAC_TXD2") (class "Default")
      (node (ref "R47") (pin "1") (pinfunction "1_1") (pintype "passive"))
    )
    (net (code "71") (name "XGMAC_TXD3") (class "Default")
      (node (ref "R46") (pin "1") (pinfunction "1_1") (pintype "passive"))
    )
    (net (code "72") (name "unconnected-(T1-TXTA-Pad15)") (class "Default")
      (node (ref "T1") (pin "15") (pinfunction "TXTA_15") (pintype "passive+no_connect"))
    )
    (net (code "73") (name "unconnected-(T1-TXTB-Pad18)") (class "Default")
      (node (ref "T1") (pin "18") (pinfunction "TXTB_18") (pintype "passive+no_connect"))
    )
    (net (code "74") (name "unconnected-(T1-TXTC-Pad21)") (class "Default")
      (node (ref "T1") (pin "21") (pinfunction "TXTC_21") (pintype "passive+no_connect"))
    )
    (net (code "75") (name "unconnected-(T1-TXTD-Pad24)") (class "Default")
      (node (ref "T1") (pin "24") (pinfunction "TXTD_24") (pintype "passive+no_connect"))
    )
    (net (code "76") (name "unconnected-(U11-NC-Pad12)") (class "Default")
      (node (ref "U11") (pin "12") (pinfunction "NC_12") (pintype "passive+no_connect"))
    )
    (net (code "77") (name "unconnected-(Y1-NC-Pad2)") (class "Default")
      (node (ref "Y1") (pin "2") (pinfunction "NC_2") (pintype "passive"))
    )
    (net (code "78") (name "unconnected-(Y1-NC-Pad4)") (class "Default")
      (node (ref "Y1") (pin "4") (pinfunction "NC_4") (pintype "passive"))
    )
  )
)
